# UI.net
KiCad netlist of a schematic drawn in Altium Designer
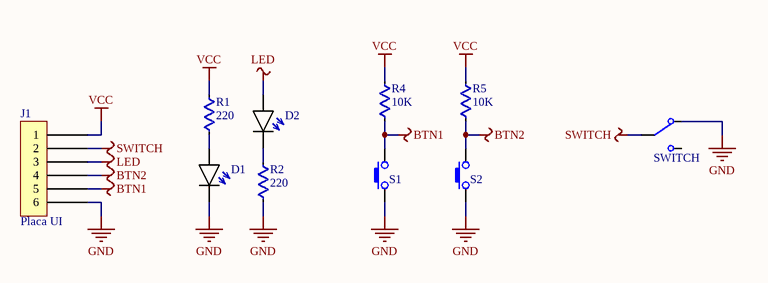
[diagram p0: UI.SchDoc]

(export (version "E")
  (design (tool "Eeschema 10.0.6"))
  (components
    (comp (ref "D1")
      (value "LED")
      (footprint "LED-3MM-YELLOW")
      (libsource (lib "AltiumLibrary") (part "LED"))
    )
    (comp (ref "D2") (value "LED") (footprint "LED-3MM-RED") (libsource (lib "AltiumLibrary") (part "LED")))
    (comp (ref "J1")
      (value "Placa UI")
      (footprint "Header 1x6")
      (libsource (lib "AltiumLibrary") (part "Header 1x6"))
    )
    (comp (ref "R1")
      (value "220")
      (footprint "RES-Axial-400mil")
      (fields (field (name "Comment") "RES"))
      (libsource (lib "AltiumLibrary") (part "RES"))
    )
    (comp (ref "R2")
      (value "220")
      (footprint "RES-Axial-400mil")
      (fields (field (name "Comment") "RES"))
      (libsource (lib "AltiumLibrary") (part "RES"))
    )
    (comp (ref "R4")
      (value "10K")
      (footprint "RES-Axial-400mil")
      (fields (field (name "Comment") "RES"))
      (libsource (lib "AltiumLibrary") (part "RES"))
    )
    (comp (ref "R5")
      (value "10K")
      (footprint "RES-Axial-400mil")
      (fields (field (name "Comment") "RES"))
      (libsource (lib "AltiumLibrary") (part "RES"))
    )
    (comp (ref "S1")
      (value "BUTTON")
      (footprint "TACT_SWITCH-SMALL-4PIN")
      (libsource (lib "AltiumLibrary") (part "BUTTON"))
    )
    (comp (ref "S2")
      (value "BUTTON")
      (footprint "TACT_SWITCH-SMALL-4PIN")
      (libsource (lib "AltiumLibrary") (part "BUTTON"))
    )
    (comp (ref "SWITCH")
      (value "SLIDE-SWITCH")
      (footprint "SWITCH")
      (libsource (lib "AltiumLibrary") (part "SLIDE-SWITCH"))
    )
  )
  (nets
    (net (code "1") (name "BTN1") (class "Default")
      (node (ref "J1") (pin "5") (pinfunction "5_5") (pintype "passive"))
      (node (ref "R4") (pin "1") (pintype "passive"))
      (node (ref "S1") (pin "2") (pintype "passive"))
    )
    (net (code "2") (name "BTN2") (class "Default")
      (node (ref "J1") (pin "4") (pinfunction "4_4") (pintype "passive"))
      (node (ref "R5") (pin "1") (pintype "passive"))
      (node (ref "S2") (pin "2") (pintype "passive"))
    )
    (net (code "3") (name "GND") (class "Default")
      (node (ref "D1") (pin "K") (pintype "passive"))
      (node (ref "J1") (pin "6") (pinfunction "6_6") (pintype "passive"))
      (node (ref "R2") (pin "1") (pintype "passive"))
      (node (ref "S1") (pin "1") (pintype "passive"))
      (node (ref "S2") (pin "1") (pintype "passive"))
      (node (ref "SWITCH") (pin "1") (pintype "power_in"))
    )
    (net (code "4") (name "LED") (class "Default")
      (node (ref "D2") (pin "A") (pintype "passive"))
      (node (ref "J1") (pin "3") (pinfunction "3_3") (pintype "passive"))
    )
    (net (code "5") (name "Net-(D1-PadA)") (class "Default")
      (node (ref "D1") (pin "A") (pintype "passive"))
      (node (ref "R1") (pin "1") (pintype "passive"))
    )
    (net (code "6") (name "Net-(D2-PadK)") (class "Default")
      (node (ref "D2") (pin "K") (pintype "passive"))
      (node (ref "R2") (pin "2") (pintype "passive"))
    )
    (net (code "7") (name "SWITCH") (class "Default")
      (node (ref "J1") (pin "2") (pinfunction "2_2") (pintype "passive"))
      (node (ref "SWITCH") (pin "2") (pintype "power_in"))
    )
    (net (code "8") (name "VCC") (class "Default")
      (node (ref "J1") (pin "1") (pinfunction "1_1") (pintype "passive"))
      (node (ref "R1") (pin "2") (pintype "passive"))
      (node (ref "R4") (pin "2") (pintype "passive"))
      (node (ref "R5") (pin "2") (pintype "passive"))
    )
    (net (code "9") (name "unconnected-(SWITCH-Pad3)") (class "Default")
      (node (ref "SWITCH") (pin "3") (pintype "power_in"))
    )
  )
)
